# PowerClocks.net
KiCad netlist of a schematic drawn in Altium Designer
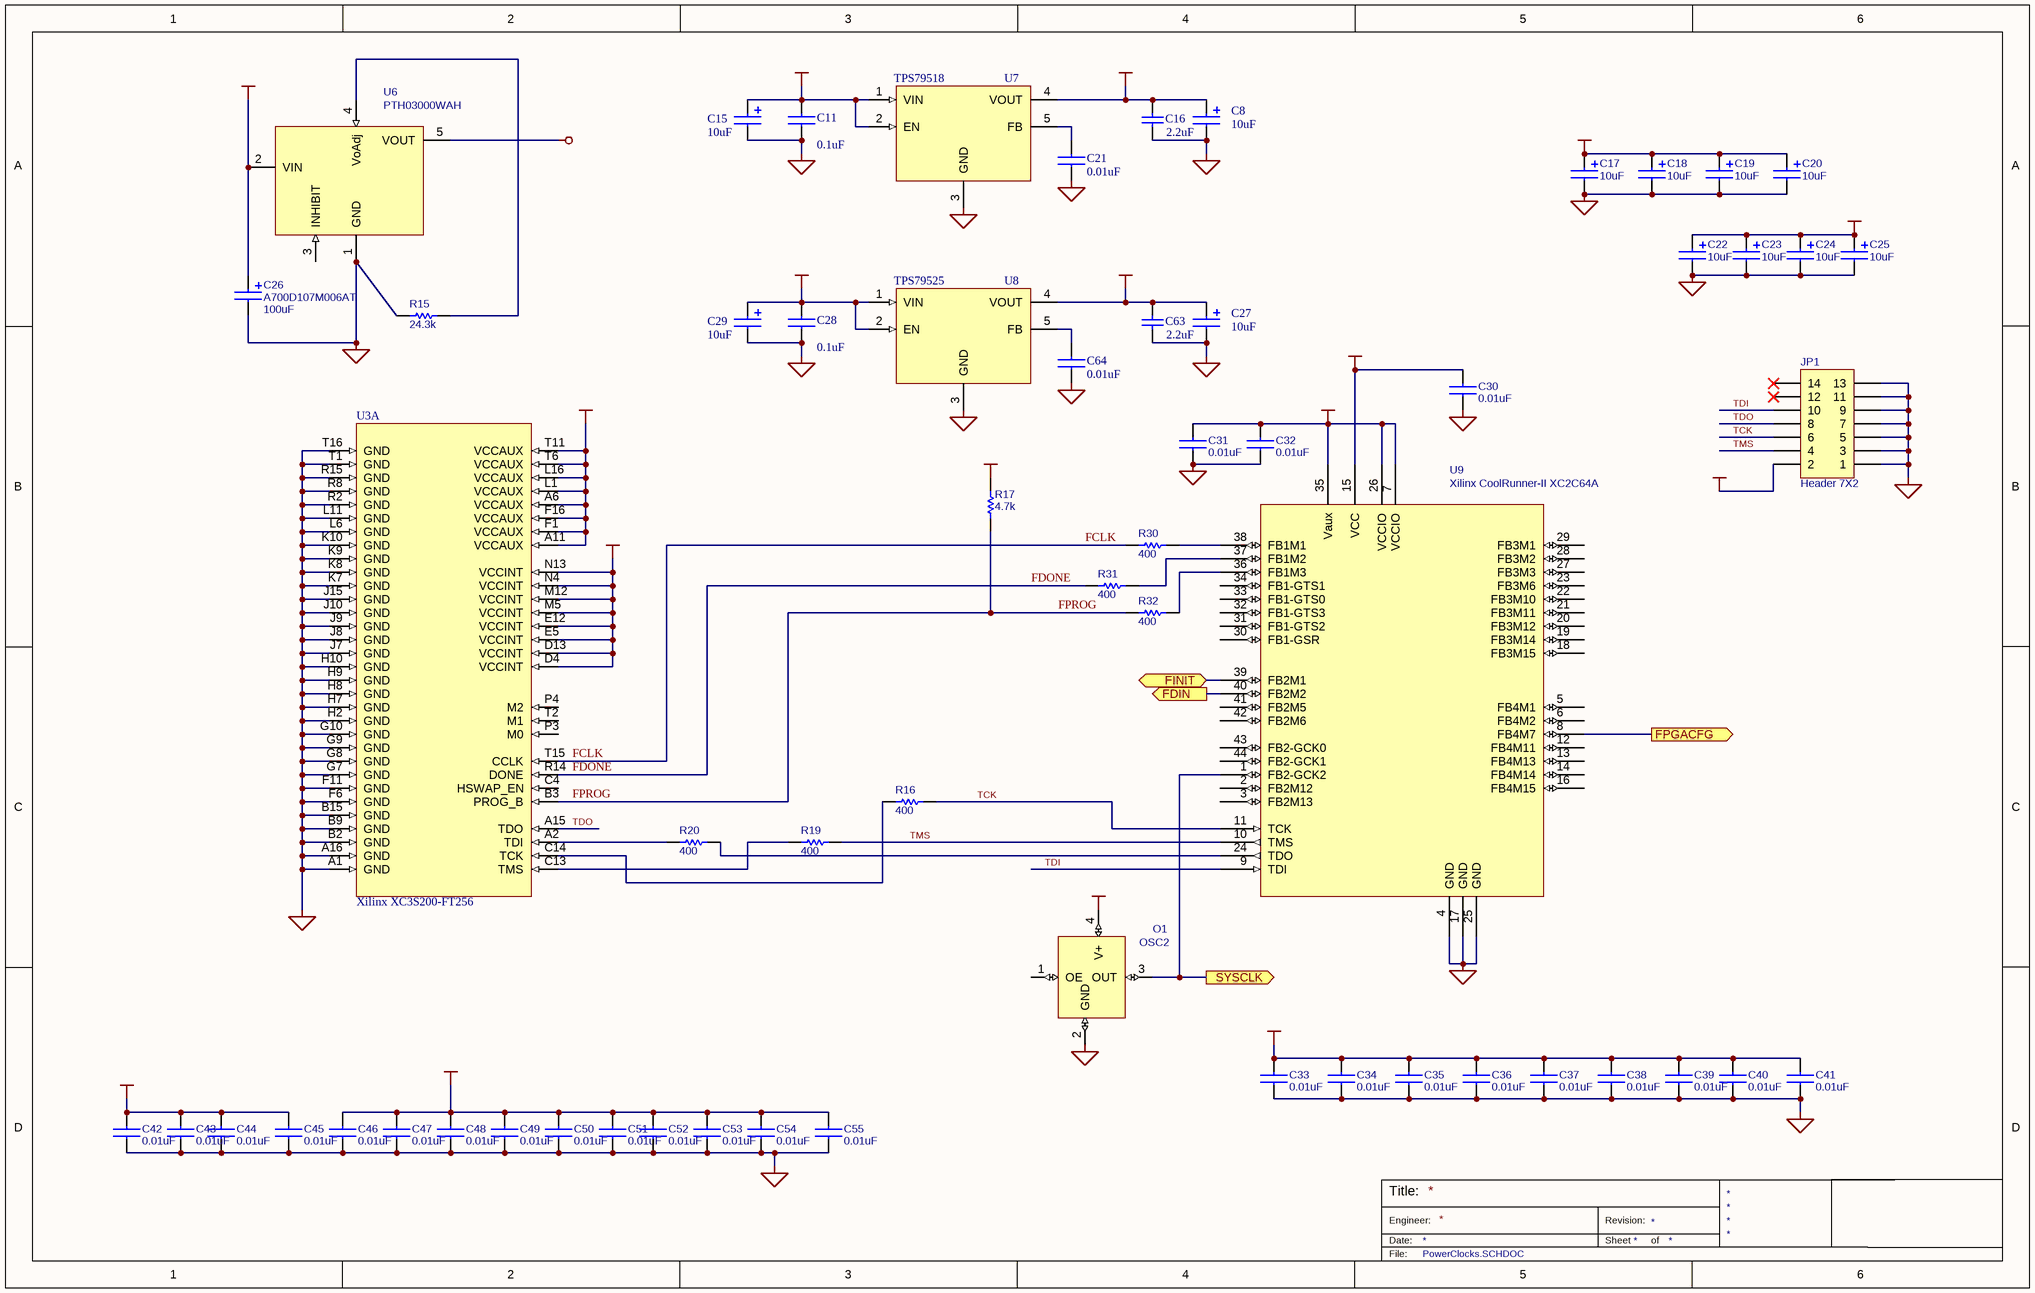
[diagram p0: PowerClocks.SCHDOC]

(export (version "E")
  (design (tool "Eeschema 10.0.6"))
  (components
    (comp (ref "C8")
      (value "10uF")
      (footprint "3216")
      (description "Standard Capacitor")
      (fields (field (name "VOLTAGE") "10V") (field (name "Comment") "POLCAP"))
      (libsource (lib "parts") (part "POLCAP"))
    )
    (comp (ref "C11")
      (value "0.1uF")
      (footprint "0603")
      (description "Standard Capacitor")
      (fields (field (name "Comment") "CAPACITOR"))
      (libsource (lib "parts") (part "CAPACITOR"))
    )
    (comp (ref "C15")
      (value "10uF")
      (footprint "3216")
      (description "Standard Capacitor")
      (fields (field (name "VOLTAGE") "10V") (field (name "Comment") "POLCAP"))
      (libsource (lib "parts") (part "POLCAP"))
    )
    (comp (ref "C16")
      (value "2.2uF")
      (footprint "1206")
      (description "Capacitor")
      (fields
        (field (name "MANUFACTURER") "Generic Components")
        (field (name "Comment") "Cap")
        (field (name "PUBLISHER") "Altium Limited")
      )
      (libsource (lib "Miscellaneous Devices") (part "Cap"))
    )
    (comp (ref "C17")
      (value "10uF")
      (footprint "3216")
      (description "Standard Capacitor")
      (fields (field (name "VOLTAGE") "10V") (field (name "Comment") "Bypass Cap"))
      (libsource (lib "parts") (part "POLCAP"))
    )
    (comp (ref "C18")
      (value "10uF")
      (footprint "3216")
      (description "Standard Capacitor")
      (fields (field (name "VOLTAGE") "10V") (field (name "Comment") "Bypass Cap"))
      (libsource (lib "parts") (part "POLCAP"))
    )
    (comp (ref "C19")
      (value "10uF")
      (footprint "3216")
      (description "Standard Capacitor")
      (fields (field (name "VOLTAGE") "10V") (field (name "Comment") "Bypass Cap"))
      (libsource (lib "parts") (part "POLCAP"))
    )
    (comp (ref "C20")
      (value "10uF")
      (footprint "3216")
      (description "Standard Capacitor")
      (fields (field (name "VOLTAGE") "10V") (field (name "Comment") "Bypass Cap"))
      (libsource (lib "parts") (part "POLCAP"))
    )
    (comp (ref "C21")
      (value "0.01uF")
      (footprint "0402")
      (description "Standard Capacitor")
      (fields (field (name "Comment") "CAPACITOR"))
      (libsource (lib "parts") (part "CAPACITOR"))
    )
    (comp (ref "C22")
      (value "10uF")
      (footprint "3216")
      (description "Standard Capacitor")
      (fields (field (name "VOLTAGE") "10V") (field (name "Comment") "Bypass Cap"))
      (libsource (lib "parts") (part "POLCAP"))
    )
    (comp (ref "C23")
      (value "10uF")
      (footprint "3216")
      (description "Standard Capacitor")
      (fields (field (name "VOLTAGE") "10V") (field (name "Comment") "Bypass Cap"))
      (libsource (lib "parts") (part "POLCAP"))
    )
    (comp (ref "C24")
      (value "10uF")
      (footprint "3216")
      (description "Standard Capacitor")
      (fields (field (name "VOLTAGE") "10V") (field (name "Comment") "Bypass Cap"))
      (libsource (lib "parts") (part "POLCAP"))
    )
    (comp (ref "C25")
      (value "10uF")
      (footprint "3216")
      (description "Standard Capacitor")
      (fields (field (name "VOLTAGE") "10V") (field (name "Comment") "Bypass Cap"))
      (libsource (lib "parts") (part "POLCAP"))
    )
    (comp (ref "C26")
      (value "A700D107M006AT")
      (footprint "7343")
      (description "Standard Capacitor")
      (fields (field (name "ALTIUM_VALUE") "100uF"))
      (libsource (lib "parts") (part "POLCAP"))
    )
    (comp (ref "C27")
      (value "10uF")
      (footprint "3216")
      (description "Standard Capacitor")
      (fields (field (name "VOLTAGE") "10V") (field (name "Comment") "POLCAP"))
      (libsource (lib "parts") (part "POLCAP"))
    )
    (comp (ref "C28")
      (value "0.1uF")
      (footprint "0603")
      (description "Standard Capacitor")
      (fields (field (name "Comment") "CAPACITOR"))
      (libsource (lib "parts") (part "CAPACITOR"))
    )
    (comp (ref "C29")
      (value "10uF")
      (footprint "3216")
      (description "Standard Capacitor")
      (fields (field (name "VOLTAGE") "10V") (field (name "Comment") "POLCAP"))
      (libsource (lib "parts") (part "POLCAP"))
    )
    (comp (ref "C30")
      (value "0.01uF")
      (footprint "0402")
      (description "Standard Capacitor")
      (fields (field (name "Comment") "CAPACITOR"))
      (libsource (lib "parts") (part "CAPACITOR"))
    )
    (comp (ref "C31")
      (value "0.01uF")
      (footprint "0402")
      (description "Standard Capacitor")
      (fields (field (name "Comment") "CAPACITOR"))
      (libsource (lib "parts") (part "CAPACITOR"))
    )
    (comp (ref "C32")
      (value "0.01uF")
      (footprint "0402")
      (description "Standard Capacitor")
      (fields (field (name "Comment") "CAPACITOR"))
      (libsource (lib "parts") (part "CAPACITOR"))
    )
    (comp (ref "C33")
      (value "0.01uF")
      (footprint "0402")
      (description "Standard Capacitor")
      (fields (field (name "Comment") "CAPACITOR"))
      (libsource (lib "parts") (part "CAPACITOR"))
    )
    (comp (ref "C34")
      (value "0.01uF")
      (footprint "0402")
      (description "Standard Capacitor")
      (fields (field (name "Comment") "CAPACITOR"))
      (libsource (lib "parts") (part "CAPACITOR"))
    )
    (comp (ref "C35")
      (value "0.01uF")
      (footprint "0402")
      (description "Standard Capacitor")
      (fields (field (name "Comment") "CAPACITOR"))
      (libsource (lib "parts") (part "CAPACITOR"))
    )
    (comp (ref "C36")
      (value "0.01uF")
      (footprint "0402")
      (description "Standard Capacitor")
      (fields (field (name "Comment") "CAPACITOR"))
      (libsource (lib "parts") (part "CAPACITOR"))
    )
    (comp (ref "C37")
      (value "0.01uF")
      (footprint "0402")
      (description "Standard Capacitor")
      (fields (field (name "Comment") "CAPACITOR"))
      (libsource (lib "parts") (part "CAPACITOR"))
    )
    (comp (ref "C38")
      (value "0.01uF")
      (footprint "0402")
      (description "Standard Capacitor")
      (fields (field (name "Comment") "CAPACITOR"))
      (libsource (lib "parts") (part "CAPACITOR"))
    )
    (comp (ref "C39")
      (value "0.01uF")
      (footprint "0402")
      (description "Standard Capacitor")
      (fields (field (name "Comment") "CAPACITOR"))
      (libsource (lib "parts") (part "CAPACITOR"))
    )
    (comp (ref "C40")
      (value "0.01uF")
      (footprint "0402")
      (description "Standard Capacitor")
      (fields (field (name "Comment") "CAPACITOR"))
      (libsource (lib "parts") (part "CAPACITOR"))
    )
    (comp (ref "C41")
      (value "0.01uF")
      (footprint "0402")
      (description "Standard Capacitor")
      (fields (field (name "Comment") "CAPACITOR"))
      (libsource (lib "parts") (part "CAPACITOR"))
    )
    (comp (ref "C42")
      (value "0.01uF")
      (footprint "0402")
      (description "Standard Capacitor")
      (fields (field (name "Comment") "CAPACITOR"))
      (libsource (lib "parts") (part "CAPACITOR"))
    )
    (comp (ref "C43")
      (value "0.01uF")
      (footprint "0402")
      (description "Standard Capacitor")
      (fields (field (name "Comment") "CAPACITOR"))
      (libsource (lib "parts") (part "CAPACITOR"))
    )
    (comp (ref "C44")
      (value "0.01uF")
      (footprint "0402")
      (description "Standard Capacitor")
      (fields (field (name "Comment") "CAPACITOR"))
      (libsource (lib "parts") (part "CAPACITOR"))
    )
    (comp (ref "C45")
      (value "0.01uF")
      (footprint "0402")
      (description "Standard Capacitor")
      (fields (field (name "Comment") "CAPACITOR"))
      (libsource (lib "parts") (part "CAPACITOR"))
    )
    (comp (ref "C46")
      (value "0.01uF")
      (footprint "0402")
      (description "Standard Capacitor")
      (fields (field (name "Comment") "CAPACITOR"))
      (libsource (lib "parts") (part "CAPACITOR"))
    )
    (comp (ref "C47")
      (value "0.01uF")
      (footprint "0402")
      (description "Standard Capacitor")
      (fields (field (name "Comment") "CAPACITOR"))
      (libsource (lib "parts") (part "CAPACITOR"))
    )
    (comp (ref "C48")
      (value "0.01uF")
      (footprint "0402")
      (description "Standard Capacitor")
      (fields (field (name "Comment") "CAPACITOR"))
      (libsource (lib "parts") (part "CAPACITOR"))
    )
    (comp (ref "C49")
      (value "0.01uF")
      (footprint "0402")
      (description "Standard Capacitor")
      (fields (field (name "Comment") "CAPACITOR"))
      (libsource (lib "parts") (part "CAPACITOR"))
    )
    (comp (ref "C50")
      (value "0.01uF")
      (footprint "0402")
      (description "Standard Capacitor")
      (fields (field (name "Comment") "CAPACITOR"))
      (libsource (lib "parts") (part "CAPACITOR"))
    )
    (comp (ref "C51")
      (value "0.01uF")
      (footprint "0402")
      (description "Standard Capacitor")
      (fields (field (name "Comment") "CAPACITOR"))
      (libsource (lib "parts") (part "CAPACITOR"))
    )
    (comp (ref "C52")
      (value "0.01uF")
      (footprint "0402")
      (description "Standard Capacitor")
      (fields (field (name "Comment") "CAPACITOR"))
      (libsource (lib "parts") (part "CAPACITOR"))
    )
    (comp (ref "C53")
      (value "0.01uF")
      (footprint "0402")
      (description "Standard Capacitor")
      (fields (field (name "Comment") "CAPACITOR"))
      (libsource (lib "parts") (part "CAPACITOR"))
    )
    (comp (ref "C54")
      (value "0.01uF")
      (footprint "0402")
      (description "Standard Capacitor")
      (fields (field (name "Comment") "CAPACITOR"))
      (libsource (lib "parts") (part "CAPACITOR"))
    )
    (comp (ref "C55")
      (value "0.01uF")
      (footprint "0402")
      (description "Standard Capacitor")
      (fields (field (name "Comment") "CAPACITOR"))
      (libsource (lib "parts") (part "CAPACITOR"))
    )
    (comp (ref "C63")
      (value "2.2uF")
      (footprint "1206")
      (description "Capacitor")
      (fields
        (field (name "MANUFACTURER") "Generic Components")
        (field (name "Comment") "Cap")
        (field (name "PUBLISHER") "Altium Limited")
      )
      (libsource (lib "Miscellaneous Devices") (part "Cap"))
    )
    (comp (ref "C64")
      (value "0.01uF")
      (footprint "0402")
      (description "Standard Capacitor")
      (fields (field (name "Comment") "CAPACITOR"))
      (libsource (lib "parts") (part "CAPACITOR"))
    )
    (comp (ref "JP1")
      (value "Header 7X2")
      (footprint "SMT 2x7 2mm HDR")
      (description "Header, 7-Pin, Dual row")
      (fields (field (name "MANUFACTURER") "Generic Components") (field (name "PUBLISHER") "Altium Limited"))
      (libsource (lib "Miscellaneous Connectors") (part "Header 7X2"))
    )
    (comp (ref "O1")
      (value "OSC2")
      (footprint "ECS-3953M")
      (description "ECS SMD Oscillator, ECS-3953M")
      (libsource (lib "parts") (part "OSC2"))
    )
    (comp (ref "R15")
      (value "24.3k")
      (footprint "1206")
      (description "Standard Passive Resistor")
      (fields (field (name "Comment") "RESISTOR"))
      (libsource (lib "parts") (part "RESISTOR"))
    )
    (comp (ref "R16")
      (value "400")
      (footprint "0603")
      (description "Standard Passive Resistor")
      (fields (field (name "Comment") "current-limiting series res"))
      (libsource (lib "parts") (part "RESISTOR"))
    )
    (comp (ref "R17")
      (value "4.7k")
      (footprint "0603")
      (description "Standard Passive Resistor")
      (fields (field (name "TOLERANCE") "1%") (field (name "Comment") "RESISTOR"))
      (libsource (lib "parts") (part "RESISTOR"))
    )
    (comp (ref "R19")
      (value "400")
      (footprint "0603")
      (description "Standard Passive Resistor")
      (fields (field (name "Comment") "current-limiting series res"))
      (libsource (lib "parts") (part "RESISTOR"))
    )
    (comp (ref "R20")
      (value "400")
      (footprint "0603")
      (description "Standard Passive Resistor")
      (fields (field (name "Comment") "current-limiting series res"))
      (libsource (lib "parts") (part "RESISTOR"))
    )
    (comp (ref "R30")
      (value "400")
      (footprint "0603")
      (description "Standard Passive Resistor")
      (fields (field (name "Comment") "current-limiting series res"))
      (libsource (lib "parts") (part "RESISTOR"))
    )
    (comp (ref "R31")
      (value "400")
      (footprint "0603")
      (description "Standard Passive Resistor")
      (fields (field (name "Comment") "current-limiting series res"))
      (libsource (lib "parts") (part "RESISTOR"))
    )
    (comp (ref "R32")
      (value "400")
      (footprint "0603")
      (description "Standard Passive Resistor")
      (fields (field (name "Comment") "current-limiting series res"))
      (libsource (lib "parts") (part "RESISTOR"))
    )
    (comp (ref "U3")
      (value "Xilinx XC3S200-FT256")
      (footprint "Xilinx FT256 BGA")
      (description "Xilinx Spartan-3 FPGA")
      (libsource (lib "parts") (part "XC3S200-FT256"))
    )
    (comp (ref "U6")
      (value "PTH03000WAH")
      (footprint "TI EUS")
      (description "TI POL converter, through-hole")
      (libsource (lib "parts") (part "PTH03000"))
    )
    (comp (ref "U7")
      (value "TPS79518")
      (footprint "SOT223-5/Simple")
      (description "TI Ultra-low-noise LDO")
      (libsource (lib "parts") (part "TPS795XX"))
    )
    (comp (ref "U8")
      (value "TPS79525")
      (footprint "SOT223-5/Simple")
      (description "TI Ultra-low-noise LDO")
      (libsource (lib "parts") (part "TPS795XX"))
    )
    (comp (ref "U9")
      (value "Xilinx CoolRunner-II XC2C64A")
      (footprint "QFP10x10-G44/G10N")
      (libsource (lib "parts") (part "XC2C64A-5VQ44C"))
    )
  )
  (nets
    (net (code "1") (name "+1.2VCC") (class "Default")
      (node (ref "C22") (pin "1") (pintype "passive"))
      (node (ref "C23") (pin "1") (pintype "passive"))
      (node (ref "C24") (pin "1") (pintype "passive"))
      (node (ref "C25") (pin "1") (pintype "passive"))
      (node (ref "C42") (pin "2") (pintype "passive"))
      (node (ref "C43") (pin "2") (pintype "passive"))
      (node (ref "C44") (pin "2") (pintype "passive"))
      (node (ref "C45") (pin "2") (pintype "passive"))
      (node (ref "U3") (pin "D13") (pinfunction "VCCINT_D13") (pintype "input"))
      (node (ref "U3") (pin "D4") (pinfunction "VCCINT_D4") (pintype "input"))
      (node (ref "U3") (pin "E12") (pinfunction "VCCINT_E12") (pintype "input"))
      (node (ref "U3") (pin "E5") (pinfunction "VCCINT_E5") (pintype "input"))
      (node (ref "U3") (pin "M12") (pinfunction "VCCINT_M12") (pintype "input"))
      (node (ref "U3") (pin "M5") (pinfunction "VCCINT_M5") (pintype "input"))
      (node (ref "U3") (pin "N13") (pinfunction "VCCINT_N13") (pintype "input"))
      (node (ref "U3") (pin "N4") (pinfunction "VCCINT_N4") (pintype "input"))
      (node (ref "U6") (pin "5") (pinfunction "VOUT_5") (pintype "power_in"))
    )
    (net (code "2") (name "+1.8VCC") (class "Default")
      (node (ref "C16") (pin "2") (pinfunction "2_2") (pintype "passive"))
      (node (ref "C30") (pin "2") (pintype "passive"))
      (node (ref "C8") (pin "1") (pintype "passive"))
      (node (ref "U7") (pin "4") (pinfunction "VOUT_4") (pintype "power_in"))
      (node (ref "U9") (pin "15") (pinfunction "VCC_15") (pintype "power_in"))
    )
    (net (code "3") (name "+2.5VCC") (class "Default")
      (node (ref "C27") (pin "1") (pintype "passive"))
      (node (ref "C46") (pin "2") (pintype "passive"))
      (node (ref "C47") (pin "2") (pintype "passive"))
      (node (ref "C48") (pin "2") (pintype "passive"))
      (node (ref "C49") (pin "2") (pintype "passive"))
      (node (ref "C50") (pin "2") (pintype "passive"))
      (node (ref "C51") (pin "2") (pintype "passive"))
      (node (ref "C52") (pin "2") (pintype "passive"))
      (node (ref "C53") (pin "2") (pintype "passive"))
      (node (ref "C54") (pin "2") (pintype "passive"))
      (node (ref "C55") (pin "2") (pintype "passive"))
      (node (ref "C63") (pin "2") (pinfunction "2_2") (pintype "passive"))
      (node (ref "R17") (pin "1") (pintype "passive"))
      (node (ref "U3") (pin "A11") (pinfunction "VCCAUX_A11") (pintype "input"))
      (node (ref "U3") (pin "A6") (pinfunction "VCCAUX_A6") (pintype "input"))
      (node (ref "U3") (pin "F1") (pinfunction "VCCAUX_F1") (pintype "input"))
      (node (ref "U3") (pin "F16") (pinfunction "VCCAUX_F16") (pintype "input"))
      (node (ref "U3") (pin "L1") (pinfunction "VCCAUX_L1") (pintype "input"))
      (node (ref "U3") (pin "L16") (pinfunction "VCCAUX_L16") (pintype "input"))
      (node (ref "U3") (pin "T11") (pinfunction "VCCAUX_T11") (pintype "input"))
      (node (ref "U3") (pin "T6") (pinfunction "VCCAUX_T6") (pintype "input"))
      (node (ref "U8") (pin "4") (pinfunction "VOUT_4") (pintype "power_in"))
    )
    (net (code "4") (name "/FCLK") (class "Default")
      (node (ref "R30") (pin "2") (pintype "passive"))
      (node (ref "U3") (pin "T15") (pinfunction "CCLK_T15") (pintype "input"))
    )
    (net (code "5") (name "/FDIN") (class "Default")
      (node (ref "U9") (pin "40") (pinfunction "FB2M2_40") (pintype "bidirectional"))
    )
    (net (code "6") (name "/FDONE") (class "Default")
      (node (ref "R31") (pin "2") (pintype "passive"))
      (node (ref "U3") (pin "R14") (pinfunction "DONE_R14") (pintype "input"))
    )
    (net (code "7") (name "/FINIT") (class "Default")
      (node (ref "U9") (pin "39") (pinfunction "FB2M1_39") (pintype "bidirectional"))
    )
    (net (code "8") (name "/FPGACFG") (class "Default")
      (node (ref "U9") (pin "8") (pinfunction "FB4M7_8") (pintype "bidirectional"))
    )
    (net (code "9") (name "/FPROG") (class "Default")
      (node (ref "R17") (pin "2") (pintype "passive"))
      (node (ref "R32") (pin "2") (pintype "passive"))
      (node (ref "U3") (pin "B3") (pinfunction "PROG_B_B3") (pintype "input"))
    )
    (net (code "10") (name "/SYSCLK") (class "Default")
      (node (ref "O1") (pin "3") (pinfunction "OUT_3") (pintype "bidirectional"))
      (node (ref "U9") (pin "1") (pinfunction "FB2-GCK2_1") (pintype "bidirectional"))
    )
    (net (code "11") (name "/TCK") (class "Default")
      (node (ref "JP1") (pin "6") (pinfunction "6_6") (pintype "passive"))
      (node (ref "R16") (pin "1") (pintype "passive"))
      (node (ref "U9") (pin "11") (pinfunction "TCK_11") (pintype "input"))
    )
    (net (code "12") (name "/TDI") (class "Default")
      (node (ref "JP1") (pin "10") (pinfunction "10_10") (pintype "passive"))
      (node (ref "U9") (pin "9") (pinfunction "TDI_9") (pintype "input"))
    )
    (net (code "13") (name "/TDO") (class "Default")
      (node (ref "JP1") (pin "8") (pinfunction "8_8") (pintype "passive"))
      (node (ref "U3") (pin "A15") (pinfunction "TDO_A15") (pintype "input"))
    )
    (net (code "14") (name "/TMS") (class "Default")
      (node (ref "JP1") (pin "4") (pinfunction "4_4") (pintype "passive"))
      (node (ref "R19") (pin "2") (pintype "passive"))
      (node (ref "U9") (pin "10") (pinfunction "TMS_10") (pintype "output"))
    )
    (net (code "15") (name "GND") (class "Default")
      (node (ref "C11") (pin "1") (pintype "passive"))
      (node (ref "C15") (pin "2") (pintype "passive"))
      (node (ref "C16") (pin "1") (pinfunction "1_1") (pintype "passive"))
      (node (ref "C17") (pin "2") (pintype "passive"))
      (node (ref "C18") (pin "2") (pintype "passive"))
      (node (ref "C19") (pin "2") (pintype "passive"))
      (node (ref "C20") (pin "2") (pintype "passive"))
      (node (ref "C21") (pin "1") (pintype "passive"))
      (node (ref "C22") (pin "2") (pintype "passive"))
      (node (ref "C23") (pin "2") (pintype "passive"))
      (node (ref "C24") (pin "2") (pintype "passive"))
      (node (ref "C25") (pin "2") (pintype "passive"))
      (node (ref "C26") (pin "2") (pintype "passive"))
      (node (ref "C27") (pin "2") (pintype "passive"))
      (node (ref "C28") (pin "1") (pintype "passive"))
      (node (ref "C29") (pin "2") (pintype "passive"))
      (node (ref "C30") (pin "1") (pintype "passive"))
      (node (ref "C31") (pin "1") (pintype "passive"))
      (node (ref "C32") (pin "1") (pintype "passive"))
      (node (ref "C33") (pin "1") (pintype "passive"))
      (node (ref "C34") (pin "1") (pintype "passive"))
      (node (ref "C35") (pin "1") (pintype "passive"))
      (node (ref "C36") (pin "1") (pintype "passive"))
      (node (ref "C37") (pin "1") (pintype "passive"))
      (node (ref "C38") (pin "1") (pintype "passive"))
      (node (ref "C39") (pin "1") (pintype "passive"))
      (node (ref "C40") (pin "1") (pintype "passive"))
      (node (ref "C41") (pin "1") (pintype "passive"))
      (node (ref "C42") (pin "1") (pintype "passive"))
      (node (ref "C43") (pin "1") (pintype "passive"))
      (node (ref "C44") (pin "1") (pintype "passive"))
      (node (ref "C45") (pin "1") (pintype "passive"))
      (node (ref "C46") (pin "1") (pintype "passive"))
      (node (ref "C47") (pin "1") (pintype "passive"))
      (node (ref "C48") (pin "1") (pintype "passive"))
      (node (ref "C49") (pin "1") (pintype "passive"))
      (node (ref "C50") (pin "1") (pintype "passive"))
      (node (ref "C51") (pin "1") (pintype "passive"))
      (node (ref "C52") (pin "1") (pintype "passive"))
      (node (ref "C53") (pin "1") (pintype "passive"))
      (node (ref "C54") (pin "1") (pintype "passive"))
      (node (ref "C55") (pin "1") (pintype "passive"))
      (node (ref "C63") (pin "1") (pinfunction "1_1") (pintype "passive"))
      (node (ref "C64") (pin "1") (pintype "passive"))
      (node (ref "C8") (pin "2") (pintype "passive"))
      (node (ref "JP1") (pin "1") (pinfunction "1_1") (pintype "passive"))
      (node (ref "JP1") (pin "11") (pinfunction "11_11") (pintype "passive"))
      (node (ref "JP1") (pin "13") (pinfunction "13_13") (pintype "passive"))
      (node (ref "JP1") (pin "3") (pinfunction "3_3") (pintype "passive"))
      (node (ref "JP1") (pin "5") (pinfunction "5_5") (pintype "passive"))
      (node (ref "JP1") (pin "7") (pinfunction "7_7") (pintype "passive"))
      (node (ref "JP1") (pin "9") (pinfunction "9_9") (pintype "passive"))
      (node (ref "O1") (pin "2") (pinfunction "GND_2") (pintype "bidirectional"))
      (node (ref "R15") (pin "2") (pintype "passive"))
      (node (ref "U3") (pin "A1") (pinfunction "GND_A1") (pintype "input"))
      (node (ref "U3") (pin "A16") (pinfunction "GND_A16") (pintype "input"))
      (node (ref "U3") (pin "B15") (pinfunction "GND_B15") (pintype "input"))
      (node (ref "U3") (pin "B2") (pinfunction "GND_B2") (pintype "input"))
      (node (ref "U3") (pin "B9") (pinfunction "GND_B9") (pintype "input"))
      (node (ref "U3") (pin "F11") (pinfunction "GND_F11") (pintype "input"))
      (node (ref "U3") (pin "F6") (pinfunction "GND_F6") (pintype "input"))
      (node (ref "U3") (pin "G10") (pinfunction "GND_G10") (pintype "input"))
      (node (ref "U3") (pin "G7") (pinfunction "GND_G7") (pintype "input"))
      (node (ref "U3") (pin "G8") (pinfunction "GND_G8") (pintype "input"))
      (node (ref "U3") (pin "G9") (pinfunction "GND_G9") (pintype "input"))
      (node (ref "U3") (pin "H10") (pinfunction "GND_H10") (pintype "input"))
      (node (ref "U3") (pin "H2") (pinfunction "GND_H2") (pintype "input"))
      (node (ref "U3") (pin "H7") (pinfunction "GND_H7") (pintype "input"))
      (node (ref "U3") (pin "H8") (pinfunction "GND_H8") (pintype "input"))
      (node (ref "U3") (pin "H9") (pinfunction "GND_H9") (pintype "input"))
      (node (ref "U3") (pin "J10") (pinfunction "GND_J10") (pintype "input"))
      (node (ref "U3") (pin "J15") (pinfunction "GND_J15") (pintype "input"))
      (node (ref "U3") (pin "J7") (pinfunction "GND_J7") (pintype "input"))
      (node (ref "U3") (pin "J8") (pinfunction "GND_J8") (pintype "input"))
      (node (ref "U3") (pin "J9") (pinfunction "GND_J9") (pintype "input"))
      (node (ref "U3") (pin "K10") (pinfunction "GND_K10") (pintype "input"))
      (node (ref "U3") (pin "K7") (pinfunction "GND_K7") (pintype "input"))
      (node (ref "U3") (pin "K8") (pinfunction "GND_K8") (pintype "input"))
      (node (ref "U3") (pin "K9") (pinfunction "GND_K9") (pintype "input"))
      (node (ref "U3") (pin "L11") (pinfunction "GND_L11") (pintype "input"))
      (node (ref "U3") (pin "L6") (pinfunction "GND_L6") (pintype "input"))
      (node (ref "U3") (pin "R15") (pinfunction "GND_R15") (pintype "input"))
      (node (ref "U3") (pin "R2") (pinfunction "GND_R2") (pintype "input"))
      (node (ref "U3") (pin "R8") (pinfunction "GND_R8") (pintype "input"))
      (node (ref "U3") (pin "T1") (pinfunction "GND_T1") (pintype "input"))
      (node (ref "U3") (pin "T16") (pinfunction "GND_T16") (pintype "input"))
      (node (ref "U6") (pin "1") (pinfunction "GND_1") (pintype "power_in"))
      (node (ref "U7") (pin "3") (pinfunction "GND_3") (pintype "power_in"))
      (node (ref "U8") (pin "3") (pinfunction "GND_3") (pintype "power_in"))
      (node (ref "U9") (pin "17") (pinfunction "GND_17") (pintype "power_in"))
      (node (ref "U9") (pin "25") (pinfunction "GND_25") (pintype "power_in"))
      (node (ref "U9") (pin "4") (pinfunction "GND_4") (pintype "power_in"))
    )
    (net (code "16") (name "Net-(U3A-TCK)") (class "Default")
      (node (ref "R16") (pin "2") (pintype "passive"))
      (node (ref "U3") (pin "C14") (pinfunction "TCK_C14") (pintype "input"))
    )
    (net (code "17") (name "Net-(U3A-TDI)") (class "Default")
      (node (ref "R20") (pin "2") (pintype "passive"))
      (node (ref "U3") (pin "A2") (pinfunction "TDI_A2") (pintype "input"))
    )
    (net (code "18") (name "Net-(U3A-TMS)") (class "Default")
      (node (ref "R19") (pin "1") (pintype "passive"))
      (node (ref "U3") (pin "C13") (pinfunction "TMS_C13") (pintype "input"))
    )
    (net (code "19") (name "Net-(U6-VoAdj)") (class "Default")
      (node (ref "R15") (pin "1") (pintype "passive"))
      (node (ref "U6") (pin "4") (pinfunction "VoAdj_4") (pintype "input"))
    )
    (net (code "20") (name "Net-(U7-FB)") (class "Default")
      (node (ref "C21") (pin "2") (pintype "passive"))
      (node (ref "U7") (pin "5") (pinfunction "FB_5") (pintype "passive"))
    )
    (net (code "21") (name "Net-(U8-FB)") (class "Default")
      (node (ref "C64") (pin "2") (pintype "passive"))
      (node (ref "U8") (pin "5") (pinfunction "FB_5") (pintype "passive"))
    )
    (net (code "22") (name "Net-(U9-FB1M1)") (class "Default")
      (node (ref "R30") (pin "1") (pintype "passive"))
      (node (ref "U9") (pin "38") (pinfunction "FB1M1_38") (pintype "bidirectional"))
    )
    (net (code "23") (name "Net-(U9-FB1M2)") (class "Default")
      (node (ref "R31") (pin "1") (pintype "passive"))
      (node (ref "U9") (pin "37") (pinfunction "FB1M2_37") (pintype "bidirectional"))
    )
    (net (code "24") (name "Net-(U9-FB1M3)") (class "Default")
      (node (ref "R32") (pin "1") (pintype "passive"))
      (node (ref "U9") (pin "36") (pinfunction "FB1M3_36") (pintype "bidirectional"))
    )
    (net (code "25") (name "Net-(U9-TDO)") (class "Default")
      (node (ref "R20") (pin "1") (pintype "passive"))
      (node (ref "U9") (pin "24") (pinfunction "TDO_24") (pintype "output"))
    )
    (net (code "26") (name "VCC") (class "Default")
      (node (ref "C11") (pin "2") (pintype "passive"))
      (node (ref "C15") (pin "1") (pintype "passive"))
      (node (ref "C17") (pin "1") (pintype "passive"))
      (node (ref "C18") (pin "1") (pintype "passive"))
      (node (ref "C19") (pin "1") (pintype "passive"))
      (node (ref "C20") (pin "1") (pintype "passive"))
      (node (ref "C26") (pin "1") (pintype "passive"))
      (node (ref "C28") (pin "2") (pintype "passive"))
      (node (ref "C29") (pin "1") (pintype "passive"))
      (node (ref "C31") (pin "2") (pintype "passive"))
      (node (ref "C32") (pin "2") (pintype "passive"))
      (node (ref "C33") (pin "2") (pintype "passive"))
      (node (ref "C34") (pin "2") (pintype "passive"))
      (node (ref "C35") (pin "2") (pintype "passive"))
      (node (ref "C36") (pin "2") (pintype "passive"))
      (node (ref "C37") (pin "2") (pintype "passive"))
      (node (ref "C38") (pin "2") (pintype "passive"))
      (node (ref "C39") (pin "2") (pintype "passive"))
      (node (ref "C40") (pin "2") (pintype "passive"))
      (node (ref "C41") (pin "2") (pintype "passive"))
      (node (ref "JP1") (pin "2") (pinfunction "2_2") (pintype "passive"))
      (node (ref "O1") (pin "4") (pinfunction "V+_4") (pintype "bidirectional"))
      (node (ref "U6") (pin "2") (pinfunction "VIN_2") (pintype "power_in"))
      (node (ref "U7") (pin "1") (pinfunction "VIN_1") (pintype "input"))
      (node (ref "U7") (pin "2") (pinfunction "EN_2") (pintype "input"))
      (node (ref "U8") (pin "1") (pinfunction "VIN_1") (pintype "input"))
      (node (ref "U8") (pin "2") (pinfunction "EN_2") (pintype "input"))
      (node (ref "U9") (pin "26") (pinfunction "VCCIO_26") (pintype "power_in"))
      (node (ref "U9") (pin "35") (pinfunction "Vaux_35") (pintype "power_in"))
      (node (ref "U9") (pin "7") (pinfunction "VCCIO_7") (pintype "power_in"))
    )
    (net (code "27") (name "unconnected-(JP1-Pad12)") (class "Default")
      (node (ref "JP1") (pin "12") (pinfunction "12_12") (pintype "passive+no_connect"))
    )
    (net (code "28") (name "unconnected-(JP1-Pad14)") (class "Default")
      (node (ref "JP1") (pin "14") (pinfunction "14_14") (pintype "passive+no_connect"))
    )
    (net (code "29") (name "unconnected-(O1-OE-Pad1)") (class "Default")
      (node (ref "O1") (pin "1") (pinfunction "OE_1") (pintype "bidirectional"))
    )
    (net (code "30") (name "unconnected-(U3A-HSWAP_EN-PadC4)") (class "Default")
      (node (ref "U3") (pin "C4") (pinfunction "HSWAP_EN_C4") (pintype "input"))
    )
    (net (code "31") (name "unconnected-(U3A-M0-PadP3)") (class "Default")
      (node (ref "U3") (pin "P3") (pinfunction "M0_P3") (pintype "input"))
    )
    (net (code "32") (name "unconnected-(U3A-M1-PadT2)") (class "Default")
      (node (ref "U3") (pin "T2") (pinfunction "M1_T2") (pintype "input"))
    )
    (net (code "33") (name "unconnected-(U3A-M2-PadP4)") (class "Default")
      (node (ref "U3") (pin "P4") (pinfunction "M2_P4") (pintype "input"))
    )
    (net (code "34") (name "unconnected-(U6-INHIBIT-Pad3)") (class "Default")
      (node (ref "U6") (pin "3") (pinfunction "INHIBIT_3") (pintype "input"))
    )
    (net (code "35") (name "unconnected-(U9-FB1-GSR-Pad30)") (class "Default")
      (node (ref "U9") (pin "30") (pinfunction "FB1-GSR_30") (pintype "bidirectional"))
    )
    (net (code "36") (name "unconnected-(U9-FB1-GTS0-Pad33)") (class "Default")
      (node (ref "U9") (pin "33") (pinfunction "FB1-GTS0_33") (pintype "bidirectional"))
    )
    (net (code "37") (name "unconnected-(U9-FB1-GTS1-Pad34)") (class "Default")
      (node (ref "U9") (pin "34") (pinfunction "FB1-GTS1_34") (pintype "bidirectional"))
    )
    (net (code "38") (name "unconnected-(U9-FB1-GTS2-Pad31)") (class "Default")
      (node (ref "U9") (pin "31") (pinfunction "FB1-GTS2_31") (pintype "bidirectional"))
    )
    (net (code "39") (name "unconnected-(U9-FB1-GTS3-Pad32)") (class "Default")
      (node (ref "U9") (pin "32") (pinfunction "FB1-GTS3_32") (pintype "bidirectional"))
    )
    (net (code "40") (name "unconnected-(U9-FB2-GCK0-Pad43)") (class "Default")
      (node (ref "U9") (pin "43") (pinfunction "FB2-GCK0_43") (pintype "bidirectional"))
    )
    (net (code "41") (name "unconnected-(U9-FB2-GCK1-Pad44)") (class "Default")
      (node (ref "U9") (pin "44") (pinfunction "FB2-GCK1_44") (pintype "bidirectional"))
    )
    (net (code "42") (name "unconnected-(U9-FB2M5-Pad41)") (class "Default")
      (node (ref "U9") (pin "41") (pinfunction "FB2M5_41") (pintype "bidirectional"))
    )
    (net (code "43") (name "unconnected-(U9-FB2M6-Pad42)") (class "Default")
      (node (ref "U9") (pin "42") (pinfunction "FB2M6_42") (pintype "bidirectional"))
    )
    (net (code "44") (name "unconnected-(U9-FB2M12-Pad2)") (class "Default")
      (node (ref "U9") (pin "2") (pinfunction "FB2M12_2") (pintype "bidirectional"))
    )
    (net (code "45") (name "unconnected-(U9-FB2M13-Pad3)") (class "Default")
      (node (ref "U9") (pin "3") (pinfunction "FB2M13_3") (pintype "bidirectional"))
    )
    (net (code "46") (name "unconnected-(U9-FB3M1-Pad29)") (class "Default")
      (node (ref "U9") (pin "29") (pinfunction "FB3M1_29") (pintype "bidirectional"))
    )
    (net (code "47") (name "unconnected-(U9-FB3M2-Pad28)") (class "Default")
      (node (ref "U9") (pin "28") (pinfunction "FB3M2_28") (pintype "bidirectional"))
    )
    (net (code "48") (name "unconnected-(U9-FB3M3-Pad27)") (class "Default")
      (node (ref "U9") (pin "27") (pinfunction "FB3M3_27") (pintype "bidirectional"))
    )
    (net (code "49") (name "unconnected-(U9-FB3M6-Pad23)") (class "Default")
      (node (ref "U9") (pin "23") (pinfunction "FB3M6_23") (pintype "bidirectional"))
    )
    (net (code "50") (name "unconnected-(U9-FB3M10-Pad22)") (class "Default")
      (node (ref "U9") (pin "22") (pinfunction "FB3M10_22") (pintype "bidirectional"))
    )
    (net (code "51") (name "unconnected-(U9-FB3M11-Pad21)") (class "Default")
      (node (ref "U9") (pin "21") (pinfunction "FB3M11_21") (pintype "bidirectional"))
    )
    (net (code "52") (name "unconnected-(U9-FB3M12-Pad20)") (class "Default")
      (node (ref "U9") (pin "20") (pinfunction "FB3M12_20") (pintype "bidirectional"))
    )
    (net (code "53") (name "unconnected-(U9-FB3M14-Pad19)") (class "Default")
      (node (ref "U9") (pin "19") (pinfunction "FB3M14_19") (pintype "bidirectional"))
    )
    (net (code "54") (name "unconnected-(U9-FB3M15-Pad18)") (class "Default")
      (node (ref "U9") (pin "18") (pinfunction "FB3M15_18") (pintype "bidirectional"))
    )
    (net (code "55") (name "unconnected-(U9-FB4M1-Pad5)") (class "Default")
      (node (ref "U9") (pin "5") (pinfunction "FB4M1_5") (pintype "bidirectional"))
    )
    (net (code "56") (name "unconnected-(U9-FB4M2-Pad6)") (class "Default")
      (node (ref "U9") (pin "6") (pinfunction "FB4M2_6") (pintype "bidirectional"))
    )
    (net (code "57") (name "unconnected-(U9-FB4M11-Pad12)") (class "Default")
      (node (ref "U9") (pin "12") (pinfunction "FB4M11_12") (pintype "bidirectional"))
    )
    (net (code "58") (name "unconnected-(U9-FB4M13-Pad13)") (class "Default")
      (node (ref "U9") (pin "13") (pinfunction "FB4M13_13") (pintype "bidirectional"))
    )
    (net (code "59") (name "unconnected-(U9-FB4M14-Pad14)") (class "Default")
      (node (ref "U9") (pin "14") (pinfunction "FB4M14_14") (pintype "bidirectional"))
    )
    (net (code "60") (name "unconnected-(U9-FB4M15-Pad16)") (class "Default")
      (node (ref "U9") (pin "16") (pinfunction "FB4M15_16") (pintype "bidirectional"))
    )
  )
)
